# sword.net
KiCad netlist of a schematic drawn in EAGLE
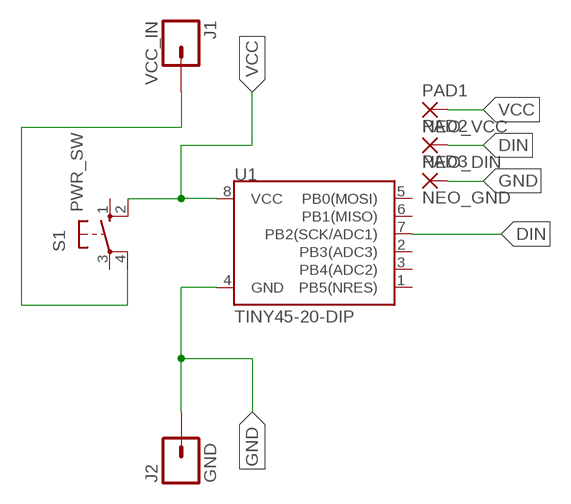
[diagram p0: schematic, sheet 1]

(export (version "E")
  (design (tool "Eeschema 10.0.6"))
  (components
    (comp (ref "J1")
      (value "VCC_IN")
      (footprint "eagle-import:1X01_LONGPAD")
      (libsource (lib "eagle-import") (part "M01PTH_LONGPAD"))
    )
    (comp (ref "J2")
      (value "GND")
      (footprint "eagle-import:1X01_LONGPAD")
      (libsource (lib "eagle-import") (part "M01PTH_LONGPAD"))
    )
    (comp (ref "PAD1")
      (value "NEO_VCC")
      (footprint "eagle-import:SMD1,27-2,54")
      (libsource (lib "eagle-import") (part "SMD2"))
    )
    (comp (ref "PAD2")
      (value "NEO_DIN")
      (footprint "eagle-import:SMD1,27-2,54")
      (libsource (lib "eagle-import") (part "SMD2"))
    )
    (comp (ref "PAD3")
      (value "NEO_GND")
      (footprint "eagle-import:SMD1,27-2,54")
      (libsource (lib "eagle-import") (part "SMD2"))
    )
    (comp (ref "S1")
      (value "PWR_SW")
      (footprint "eagle-import:B3F-10XX")
      (fields (field (name "MPN") "B3F-1000"))
      (libsource (lib "eagle-import") (part "10-XX"))
    )
    (comp (ref "U1")
      (value "TINY45-20-DIP")
      (footprint "eagle-import:DIP08")
      (libsource (lib "eagle-import") (part "ATTINY45TINY45-20-DIP"))
    )
  )
  (nets
    (net (code "1") (name "DIN") (class "Default")
      (node (ref "PAD2") (pin "1") (pinfunction "P_1") (pintype "passive"))
      (node (ref "U1") (pin "7") (pinfunction "PB2(SCK/ADC1)_7") (pintype "bidirectional"))
    )
    (net (code "2") (name "GND") (class "Default")
      (node (ref "J2") (pin "1") (pinfunction "1_1") (pintype "passive"))
      (node (ref "PAD3") (pin "1") (pinfunction "P_1") (pintype "passive"))
      (node (ref "U1") (pin "4") (pinfunction "GND_4") (pintype "bidirectional"))
    )
    (net (code "3") (name "Net-(S1-P1)") (class "Default")
      (node (ref "J1") (pin "1") (pinfunction "1_1") (pintype "passive"))
      (node (ref "S1") (pin "4") (pinfunction "P1_4") (pintype "passive"))
    )
    (net (code "4") (name "VCC") (class "Default")
      (node (ref "PAD1") (pin "1") (pinfunction "P_1") (pintype "passive"))
      (node (ref "S1") (pin "2") (pinfunction "S1_2") (pintype "passive"))
      (node (ref "U1") (pin "8") (pinfunction "VCC_8") (pintype "bidirectional"))
    )
    (net (code "5") (name "unconnected-(S1-P-Pad3)") (class "Default")
      (node (ref "S1") (pin "3") (pinfunction "P_3") (pintype "passive"))
    )
    (net (code "6") (name "unconnected-(S1-S-Pad1)") (class "Default")
      (node (ref "S1") (pin "1") (pinfunction "S_1") (pintype "passive"))
    )
    (net (code "7") (name "unconnected-(U1-PB0(MOSI)-Pad5)") (class "Default")
      (node (ref "U1") (pin "5") (pinfunction "PB0(MOSI)_5") (pintype "bidirectional"))
    )
    (net (code "8") (name "unconnected-(U1-PB1(MISO)-Pad6)") (class "Default")
      (node (ref "U1") (pin "6") (pinfunction "PB1(MISO)_6") (pintype "bidirectional"))
    )
    (net (code "9") (name "unconnected-(U1-PB3(ADC3)-Pad2)") (class "Default")
      (node (ref "U1") (pin "2") (pinfunction "PB3(ADC3)_2") (pintype "bidirectional"))
    )
    (net (code "10") (name "unconnected-(U1-PB4(ADC2)-Pad3)") (class "Default")
      (node (ref "U1") (pin "3") (pinfunction "PB4(ADC2)_3") (pintype "bidirectional"))
    )
    (net (code "11") (name "unconnected-(U1-PB5(NRES)-Pad1)") (class "Default")
      (node (ref "U1") (pin "1") (pinfunction "PB5(NRES)_1") (pintype "bidirectional"))
    )
  )
)
